# SAMDi_version6_sot223.net
KiCad netlist of a schematic drawn in EAGLE
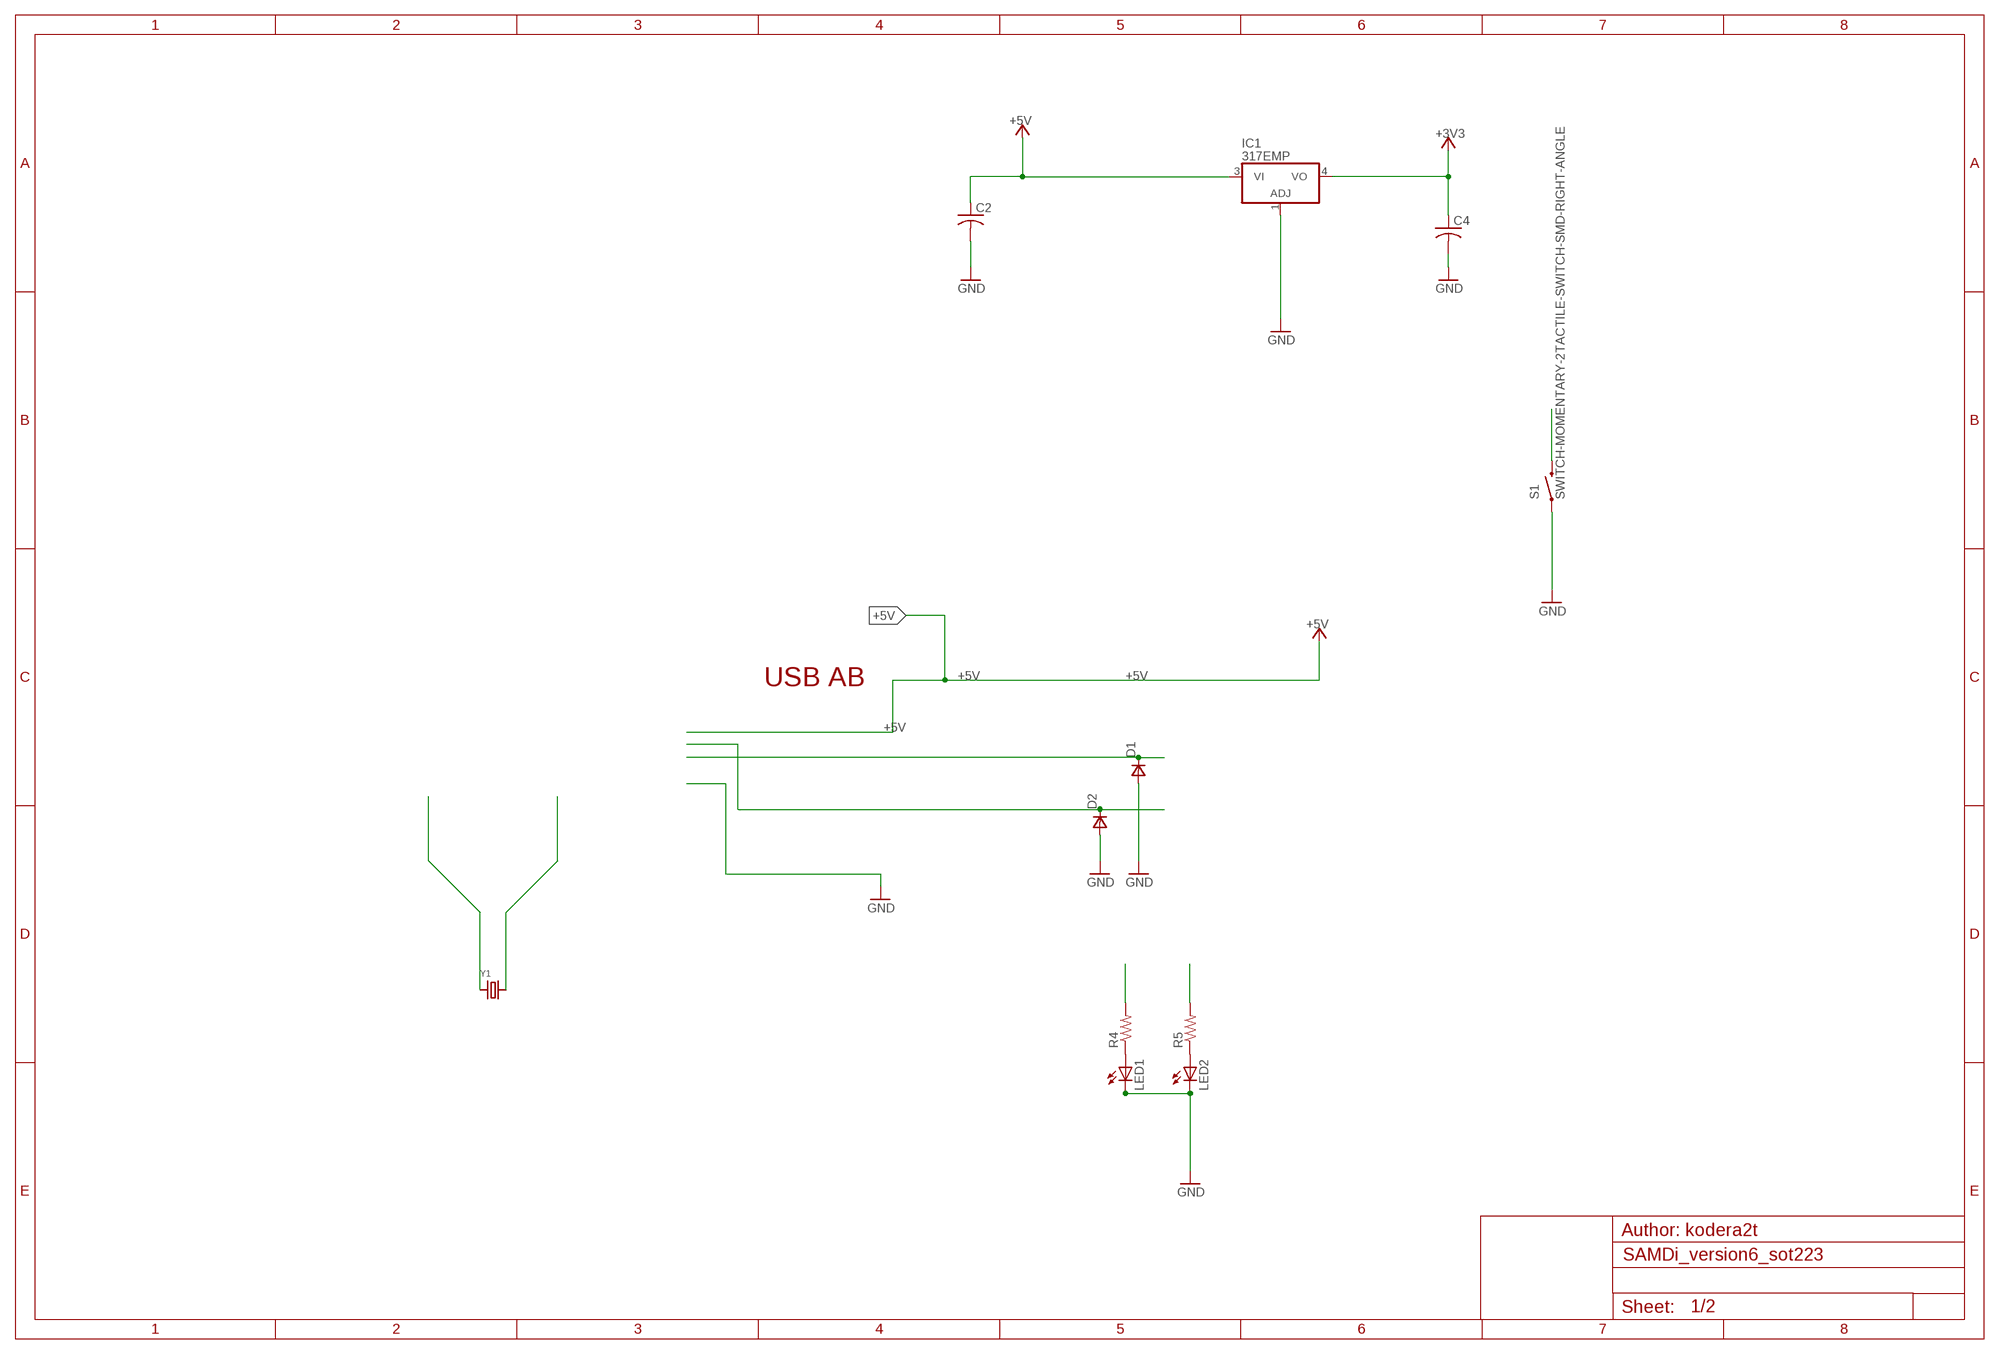
[diagram p0: schematic, sheet 1]
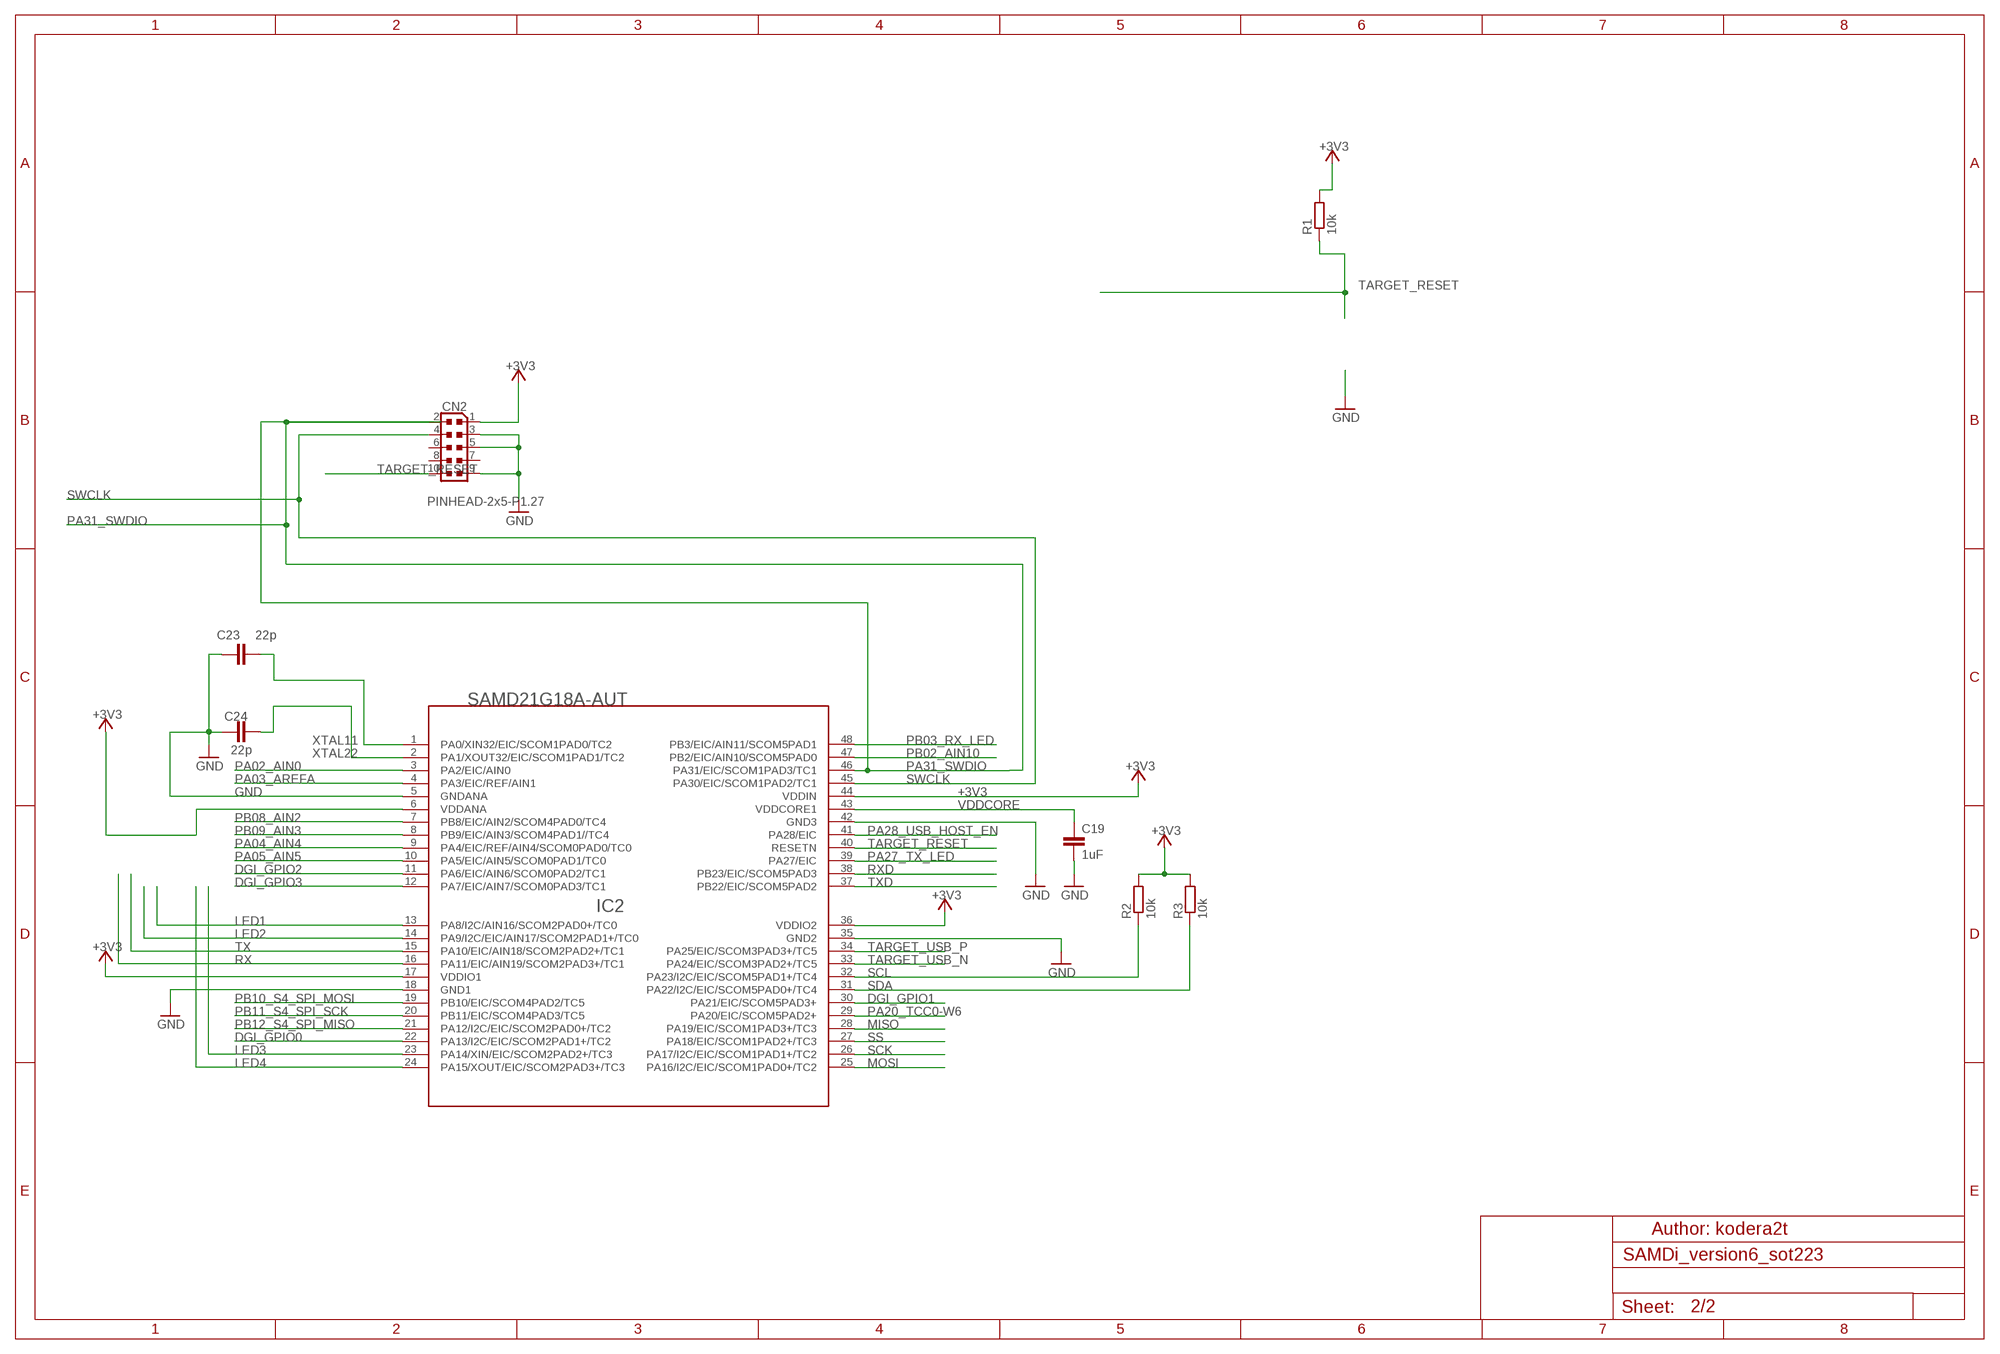
[diagram p1: schematic, sheet 2]

(export (version "E")
  (design (tool "Eeschema 10.0.6"))
  (components
    (comp (ref "C2")
      (value "C-USC0603")
      (footprint "eagle-import:C0603")
      (libsource (lib "eagle-import") (part "C-USC0603"))
    )
    (comp (ref "C4")
      (value "C-USC0603")
      (footprint "eagle-import:C0603")
      (libsource (lib "eagle-import") (part "C-USC0603"))
    )
    (comp (ref "D1")
      (value "DSOD323")
      (footprint "eagle-import:SOD323")
      (fields (field (name "MPN") "CDSOD323-T05C"))
      (libsource (lib "eagle-import") (part "DSOD323"))
    )
    (comp (ref "D2")
      (value "DSOD323")
      (footprint "eagle-import:SOD323")
      (fields (field (name "MPN") "CDSOD323-T05C"))
      (libsource (lib "eagle-import") (part "DSOD323"))
    )
    (comp (ref "IC1")
      (value "317EMP")
      (footprint "eagle-import:SOT223")
      (libsource (lib "eagle-import") (part "317EMP"))
    )
    (comp (ref "LED1")
      (value "LEDCHIP-LED0603")
      (footprint "eagle-import:CHIP-LED0603")
      (libsource (lib "eagle-import") (part "LEDCHIP-LED0603"))
    )
    (comp (ref "LED2")
      (value "LEDCHIP-LED0603")
      (footprint "eagle-import:CHIP-LED0603")
      (libsource (lib "eagle-import") (part "LEDCHIP-LED0603"))
    )
    (comp (ref "R4")
      (value "R-US_R0603")
      (footprint "eagle-import:R0603")
      (libsource (lib "eagle-import") (part "R-US_R0603"))
    )
    (comp (ref "R5")
      (value "R-US_R0603")
      (footprint "eagle-import:R0603")
      (libsource (lib "eagle-import") (part "R-US_R0603"))
    )
    (comp (ref "S1")
      (value "SWITCH-MOMENTARY-2TACTILE-SWITCH-SMD-RIGHT-ANGLE")
      (footprint "eagle-import:TACTILE_SWITCH-SMD-RIGHT-ANGLE")
      (libsource (lib "eagle-import") (part "SWITCH-MOMENTARY-2TACTILE-SWITCH-SMD-RIGHT-ANGLE"))
    )
    (comp (ref "Y1")
      (value "CRYSTALTHIN32K")
      (footprint "eagle-import:CRYSTAL_4.9X1.8")
      (libsource (lib "eagle-import") (part "CRYSTALTHIN32K"))
    )
    (comp (ref "C19")
      (value "1uF")
      (footprint "eagle-import:C0603-ROUND")
      (fields (field (name "PART_NUMBER") "1uF_0603/GRM188R61E105KA12D"))
      (libsource (lib "eagle-import") (part "0006_1UF_0603/GRM188R61E105KA12D"))
    )
    (comp (ref "C23")
      (value "22p")
      (footprint "eagle-import:C0603-ROUND")
      (fields (field (name "PART_NUMBER") "22pF_0603"))
      (libsource (lib "eagle-import") (part "0014_22PF_0603"))
    )
    (comp (ref "C24")
      (value "22p")
      (footprint "eagle-import:C0603-ROUND")
      (fields (field (name "PART_NUMBER") "22pF_0603"))
      (libsource (lib "eagle-import") (part "0014_22PF_0603"))
    )
    (comp (ref "CN2")
      (value "PINHEAD-2x5-P1.27")
      (footprint "eagle-import:PINHEAD_2X05_127")
      (libsource (lib "eagle-import") (part "0171_PH127-205DF055G00AROUND-PADS"))
    )
    (comp (ref "IC2")
      (value "SAMD21G18A-AUT")
      (footprint "eagle-import:TQFP48-7X7")
      (libsource (lib "eagle-import") (part "1792_SAMD21G18A-AUT"))
    )
    (comp (ref "R1")
      (value "10k")
      (footprint "eagle-import:R0603-ROUND")
      (fields (field (name "PART_NUMBER") "CR0603JW103L"))
      (libsource (lib "eagle-import") (part "0028_CR0603JW103L"))
    )
    (comp (ref "R2")
      (value "10k")
      (footprint "eagle-import:R0603-ROUND")
      (fields (field (name "PART_NUMBER") "CR0603JW103L"))
      (libsource (lib "eagle-import") (part "0028_CR0603JW103L"))
    )
    (comp (ref "R3")
      (value "10k")
      (footprint "eagle-import:R0603-ROUND")
      (fields (field (name "PART_NUMBER") "CR0603JW103L"))
      (libsource (lib "eagle-import") (part "0028_CR0603JW103L"))
    )
  )
  (nets
    (net (code "1") (name "+3V3") (class "Default")
      (node (ref "C4") (pin "1") (pinfunction "1_1") (pintype "passive"))
      (node (ref "CN2") (pin "1") (pinfunction "1_1") (pintype "passive"))
      (node (ref "IC1") (pin "4") (pinfunction "VO_4") (pintype "passive"))
      (node (ref "IC2") (pin "17") (pinfunction "VDDIO1_17") (pintype "power_in"))
      (node (ref "IC2") (pin "36") (pinfunction "VDDIO2_36") (pintype "power_in"))
      (node (ref "IC2") (pin "44") (pinfunction "VDDIN_44") (pintype "power_in"))
      (node (ref "IC2") (pin "6") (pinfunction "VDDANA_6") (pintype "power_in"))
      (node (ref "R1") (pin "2") (pinfunction "2_2") (pintype "passive"))
      (node (ref "R2") (pin "2") (pinfunction "2_2") (pintype "passive"))
      (node (ref "R3") (pin "2") (pinfunction "2_2") (pintype "passive"))
    )
    (net (code "2") (name "+5V") (class "Default")
      (node (ref "C2") (pin "1") (pinfunction "1_1") (pintype "passive"))
      (node (ref "IC1") (pin "3") (pinfunction "VI_3") (pintype "input"))
    )
    (net (code "3") (name "DGI_GPIO0") (class "Default")
      (node (ref "IC2") (pin "22") (pinfunction "PA13/I2C/EIC/SCOM2PAD1+/TC2_22") (pintype "bidirectional"))
    )
    (net (code "4") (name "DGI_GPIO1") (class "Default")
      (node (ref "IC2") (pin "30") (pinfunction "PA21/EIC/SCOM5PAD3+_30") (pintype "bidirectional"))
    )
    (net (code "5") (name "DGI_GPIO2") (class "Default")
      (node (ref "IC2") (pin "11") (pinfunction "PA6/EIC/AIN6/SCOM0PAD2/TC1_11") (pintype "bidirectional"))
    )
    (net (code "6") (name "DGI_GPIO3") (class "Default")
      (node (ref "IC2") (pin "12") (pinfunction "PA7/EIC/AIN7/SCOM0PAD3/TC1_12") (pintype "bidirectional"))
    )
    (net (code "7") (name "GND") (class "Default")
      (node (ref "C19") (pin "2") (pinfunction "2_2") (pintype "passive"))
      (node (ref "C2") (pin "2") (pinfunction "2_2") (pintype "passive"))
      (node (ref "C23") (pin "1") (pinfunction "1_1") (pintype "passive"))
      (node (ref "C24") (pin "1") (pinfunction "1_1") (pintype "passive"))
      (node (ref "C4") (pin "2") (pinfunction "2_2") (pintype "passive"))
      (node (ref "CN2") (pin "3") (pinfunction "3_3") (pintype "passive"))
      (node (ref "CN2") (pin "5") (pinfunction "5_5") (pintype "passive"))
      (node (ref "CN2") (pin "9") (pinfunction "9_9") (pintype "passive"))
      (node (ref "D1") (pin "2") (pinfunction "A_2") (pintype "passive"))
      (node (ref "D2") (pin "2") (pinfunction "A_2") (pintype "passive"))
      (node (ref "IC1") (pin "1") (pinfunction "ADJ_1") (pintype "input"))
      (node (ref "IC2") (pin "18") (pinfunction "GND1_18") (pintype "power_in"))
      (node (ref "IC2") (pin "35") (pinfunction "GND2_35") (pintype "power_in"))
      (node (ref "IC2") (pin "42") (pinfunction "GND3_42") (pintype "power_in"))
      (node (ref "IC2") (pin "5") (pinfunction "GNDANA_5") (pintype "power_in"))
      (node (ref "LED1") (pin "C") (pinfunction "C_C") (pintype "passive"))
      (node (ref "LED2") (pin "C") (pinfunction "C_C") (pintype "passive"))
      (node (ref "S1") (pin "1") (pinfunction "1_1") (pintype "passive"))
    )
    (net (code "8") (name "LED1") (class "Default")
      (node (ref "IC2") (pin "13") (pinfunction "PA8/I2C/AIN16/SCOM2PAD0+/TC0_13") (pintype "bidirectional"))
      (node (ref "R4") (pin "2") (pinfunction "2_2") (pintype "passive"))
    )
    (net (code "9") (name "LED2") (class "Default")
      (node (ref "IC2") (pin "14") (pinfunction "PA9/I2C/EIC/AIN17/SCOM2PAD1+/TC0_14") (pintype "bidirectional"))
      (node (ref "R5") (pin "2") (pinfunction "2_2") (pintype "passive"))
    )
    (net (code "10") (name "LED3") (class "Default")
      (node (ref "IC2") (pin "23") (pinfunction "PA14/XIN/EIC/SCOM2PAD2+/TC3_23") (pintype "bidirectional"))
    )
    (net (code "11") (name "LED4") (class "Default")
      (node (ref "IC2") (pin "24") (pinfunction "PA15/XOUT/EIC/SCOM2PAD3+/TC3_24") (pintype "bidirectional"))
    )
    (net (code "12") (name "MISO") (class "Default")
      (node (ref "IC2") (pin "28") (pinfunction "PA19/EIC/SCOM1PAD3+/TC3_28") (pintype "bidirectional"))
    )
    (net (code "13") (name "MOSI") (class "Default")
      (node (ref "IC2") (pin "25") (pinfunction "PA16/I2C/EIC/SCOM1PAD0+/TC2_25") (pintype "bidirectional"))
    )
    (net (code "14") (name "Net-(LED1-PadA)") (class "Default")
      (node (ref "LED1") (pin "A") (pinfunction "A_A") (pintype "passive"))
      (node (ref "R4") (pin "1") (pinfunction "1_1") (pintype "passive"))
    )
    (net (code "15") (name "Net-(LED2-PadA)") (class "Default")
      (node (ref "LED2") (pin "A") (pinfunction "A_A") (pintype "passive"))
      (node (ref "R5") (pin "1") (pinfunction "1_1") (pintype "passive"))
    )
    (net (code "16") (name "PA02_AIN0") (class "Default")
      (node (ref "IC2") (pin "3") (pinfunction "PA2/EIC/AIN0_3") (pintype "bidirectional"))
    )
    (net (code "17") (name "PA03_AREFA") (class "Default")
      (node (ref "IC2") (pin "4") (pinfunction "PA3/EIC/REF/AIN1_4") (pintype "bidirectional"))
    )
    (net (code "18") (name "PA04_AIN4") (class "Default")
      (node (ref "IC2") (pin "9") (pinfunction "PA4/EIC/REF/AIN4/SCOM0PAD0/TC0_9") (pintype "bidirectional"))
    )
    (net (code "19") (name "PA05_AIN5") (class "Default")
      (node (ref "IC2") (pin "10") (pinfunction "PA5/EIC/AIN5/SCOM0PAD1/TC0_10") (pintype "bidirectional"))
    )
    (net (code "20") (name "PA20_TCC0-W6") (class "Default")
      (node (ref "IC2") (pin "29") (pinfunction "PA20/EIC/SCOM5PAD2+_29") (pintype "bidirectional"))
    )
    (net (code "21") (name "PA27_TX_LED") (class "Default")
      (node (ref "IC2") (pin "39") (pinfunction "PA27/EIC_39") (pintype "bidirectional"))
    )
    (net (code "22") (name "PA28_USB_HOST_EN") (class "Default")
      (node (ref "IC2") (pin "41") (pinfunction "PA28/EIC_41") (pintype "bidirectional"))
    )
    (net (code "23") (name "PA31_SWDIO") (class "Default")
      (node (ref "CN2") (pin "2") (pinfunction "2_2") (pintype "passive"))
      (node (ref "IC2") (pin "46") (pinfunction "PA31/EIC/SCOM1PAD3/TC1_46") (pintype "bidirectional"))
    )
    (net (code "24") (name "PB02_AIN10") (class "Default")
      (node (ref "IC2") (pin "47") (pinfunction "PB2/EIC/AIN10/SCOM5PAD0_47") (pintype "bidirectional"))
    )
    (net (code "25") (name "PB03_RX_LED") (class "Default")
      (node (ref "IC2") (pin "48") (pinfunction "PB3/EIC/AIN11/SCOM5PAD1_48") (pintype "bidirectional"))
    )
    (net (code "26") (name "PB08_AIN2") (class "Default")
      (node (ref "IC2") (pin "7") (pinfunction "PB8/EIC/AIN2/SCOM4PAD0/TC4_7") (pintype "bidirectional"))
    )
    (net (code "27") (name "PB09_AIN3") (class "Default")
      (node (ref "IC2") (pin "8") (pinfunction "PB9/EIC/AIN3/SCOM4PAD1//TC4_8") (pintype "bidirectional"))
    )
    (net (code "28") (name "PB10_S4_SPI_MOSI") (class "Default")
      (node (ref "IC2") (pin "19") (pinfunction "PB10/EIC/SCOM4PAD2/TC5_19") (pintype "bidirectional"))
    )
    (net (code "29") (name "PB11_S4_SPI_SCK") (class "Default")
      (node (ref "IC2") (pin "20") (pinfunction "PB11/EIC/SCOM4PAD3/TC5_20") (pintype "bidirectional"))
    )
    (net (code "30") (name "PB12_S4_SPI_MISO") (class "Default")
      (node (ref "IC2") (pin "21") (pinfunction "PA12/I2C/EIC/SCOM2PAD0+/TC2_21") (pintype "bidirectional"))
    )
    (net (code "31") (name "RX") (class "Default")
      (node (ref "IC2") (pin "16") (pinfunction "PA11/EIC/AIN19/SCOM2PAD3+/TC1_16") (pintype "bidirectional"))
    )
    (net (code "32") (name "RXD") (class "Default")
      (node (ref "IC2") (pin "38") (pinfunction "PB23/EIC/SCOM5PAD3_38") (pintype "bidirectional"))
    )
    (net (code "33") (name "SCK") (class "Default")
      (node (ref "IC2") (pin "26") (pinfunction "PA17/I2C/EIC/SCOM1PAD1+/TC2_26") (pintype "bidirectional"))
    )
    (net (code "34") (name "SCL") (class "Default")
      (node (ref "IC2") (pin "32") (pinfunction "PA23/I2C/EIC/SCOM5PAD1+/TC4_32") (pintype "bidirectional"))
      (node (ref "R2") (pin "1") (pinfunction "1_1") (pintype "passive"))
    )
    (net (code "35") (name "SDA") (class "Default")
      (node (ref "IC2") (pin "31") (pinfunction "PA22/I2C/EIC/SCOM5PAD0+/TC4_31") (pintype "bidirectional"))
      (node (ref "R3") (pin "1") (pinfunction "1_1") (pintype "passive"))
    )
    (net (code "36") (name "SS") (class "Default")
      (node (ref "IC2") (pin "27") (pinfunction "PA18/EIC/SCOM1PAD2+/TC3_27") (pintype "bidirectional"))
    )
    (net (code "37") (name "SWCLK") (class "Default")
      (node (ref "CN2") (pin "4") (pinfunction "4_4") (pintype "passive"))
      (node (ref "IC2") (pin "45") (pinfunction "PA30/EIC/SCOM1PAD2/TC1_45") (pintype "bidirectional"))
    )
    (net (code "38") (name "TARGET_RESET") (class "Default")
      (node (ref "CN2") (pin "10") (pinfunction "10_10") (pintype "passive"))
      (node (ref "IC2") (pin "40") (pinfunction "RESETN_40") (pintype "bidirectional"))
      (node (ref "R1") (pin "1") (pinfunction "1_1") (pintype "passive"))
      (node (ref "S1") (pin "2") (pinfunction "2_2") (pintype "passive"))
    )
    (net (code "39") (name "TARGET_USB_N") (class "Default")
      (node (ref "D2") (pin "1") (pinfunction "C_1") (pintype "passive"))
      (node (ref "IC2") (pin "33") (pinfunction "PA24/EIC/SCOM3PAD2+/TC5_33") (pintype "bidirectional"))
    )
    (net (code "40") (name "TARGET_USB_P") (class "Default")
      (node (ref "D1") (pin "1") (pinfunction "C_1") (pintype "passive"))
      (node (ref "IC2") (pin "34") (pinfunction "PA25/EIC/SCOM3PAD3+/TC5_34") (pintype "bidirectional"))
    )
    (net (code "41") (name "TX") (class "Default")
      (node (ref "IC2") (pin "15") (pinfunction "PA10/EIC/AIN18/SCOM2PAD2+/TC1_15") (pintype "bidirectional"))
    )
    (net (code "42") (name "TXD") (class "Default")
      (node (ref "IC2") (pin "37") (pinfunction "PB22/EIC/SCOM5PAD2_37") (pintype "bidirectional"))
    )
    (net (code "43") (name "VDDCORE") (class "Default")
      (node (ref "C19") (pin "1") (pinfunction "1_1") (pintype "passive"))
      (node (ref "IC2") (pin "43") (pinfunction "VDDCORE1_43") (pintype "input"))
    )
    (net (code "44") (name "XTAL11") (class "Default")
      (node (ref "C23") (pin "2") (pinfunction "2_2") (pintype "passive"))
      (node (ref "IC2") (pin "1") (pinfunction "PA0/XIN32/EIC/SCOM1PAD0/TC2_1") (pintype "bidirectional"))
      (node (ref "Y1") (pin "2") (pinfunction "2_2") (pintype "passive"))
    )
    (net (code "45") (name "XTAL22") (class "Default")
      (node (ref "C24") (pin "2") (pinfunction "2_2") (pintype "passive"))
      (node (ref "IC2") (pin "2") (pinfunction "PA1/XOUT32/EIC/SCOM1PAD1/TC2_2") (pintype "bidirectional"))
      (node (ref "Y1") (pin "1") (pinfunction "1_1") (pintype "passive"))
    )
    (net (code "46") (name "unconnected-(CN2-Pad6)") (class "Default")
      (node (ref "CN2") (pin "6") (pinfunction "6_6") (pintype "passive"))
    )
    (net (code "47") (name "unconnected-(CN2-Pad7)") (class "Default")
      (node (ref "CN2") (pin "7") (pinfunction "7_7") (pintype "passive"))
    )
    (net (code "48") (name "unconnected-(CN2-Pad8)") (class "Default")
      (node (ref "CN2") (pin "8") (pinfunction "8_8") (pintype "passive"))
    )
  )
)
